# 3xOuts.net
KiCad netlist of a schematic drawn in Altium Designer
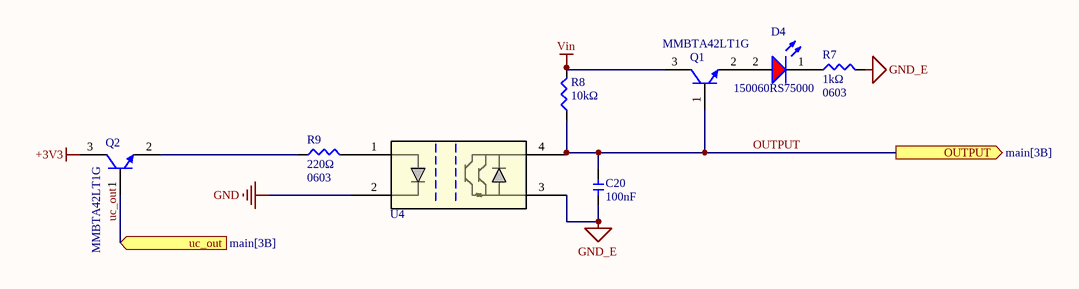
[diagram p0: 3xOuts.SchDoc]

(export (version "E")
  (design (tool "Eeschema 10.0.6"))
  (components
    (comp (ref "C20")
      (value "100nF")
      (footprint "0603_cap")
      (fields (field (name "Comment") "0603_100nF"))
      (libsource (lib "generic") (part "0603_100nF"))
    )
    (comp (ref "D4")
      (value "150060RS75000")
      (footprint "WL-SMCW_0603_150060xx75000")
      (libsource (lib "Altium Content Vault") (part "LED_Red_2A-1K"))
    )
    (comp (ref "Q1")
      (value "MMBTA42LT1G")
      (footprint "ONSC-SOT-23-3-318-08_V")
      (description "High Voltage Transistor, NPN Silicon, 3-Pin SOT-23, Pb-Free, Tape and Reel")
      (fields (field (name "MANUFACTURER") "On Semiconductor"))
      (libsource (lib "Altium Content Vault") (part "ONSC-NPN-B1E2C3-3"))
    )
    (comp (ref "Q2")
      (value "MMBTA42LT1G")
      (footprint "ONSC-SOT-23-3-318-08_V")
      (description "High Voltage Transistor, NPN Silicon, 3-Pin SOT-23, Pb-Free, Tape and Reel")
      (fields (field (name "MANUFACTURER") "On Semiconductor"))
      (libsource (lib "Altium Content Vault") (part "ONSC-NPN-B1E2C3-3"))
    )
    (comp (ref "R7")
      (value "1kΩ")
      (footprint "0603-smd")
      (fields (field (name "POWER") "W") (field (name "PACKAGE") "0603") (field (name "Comment") "0603_1K"))
      (libsource (lib "generic") (part "0603_1K"))
    )
    (comp (ref "R8")
      (value "10kΩ")
      (footprint "0603-smd")
      (fields (field (name "POWER") "W") (field (name "Comment") "0603_10K"))
      (libsource (lib "generic") (part "0603_10K"))
    )
    (comp (ref "R9")
      (value "220Ω")
      (footprint "0603-smd")
      (fields (field (name "POWER") "W") (field (name "PACKAGE") "0603") (field (name "Comment") "0603_220R"))
      (libsource (lib "generic") (part "0603_220R"))
    )
    (comp (ref "U4")
      (value "LTV-352T")
      (footprint "IC4_LTV-352T_LTO-M")
      (description "LTV Series Single Channel 300V 3750 Vrms Transistor Output Optocoupler SMT DIP-4")
      (fields (field (name "MANUFACTURER") "Vishay Lite-On"))
      (libsource (lib "generic") (part "LTV-352T"))
    )
  )
  (nets
    (net (code "1") (name "+3V3") (class "Default")
      (node (ref "Q2") (pin "3") (pinfunction "C_3") (pintype "passive"))
    )
    (net (code "2") (name "/OUTPUT") (class "Default")
      (node (ref "C20") (pin "2") (pinfunction "2_2") (pintype "passive"))
      (node (ref "Q1") (pin "1") (pinfunction "B_1") (pintype "passive"))
      (node (ref "R8") (pin "1") (pinfunction "1_1") (pintype "passive"))
      (node (ref "U4") (pin "4") (pinfunction "4_4") (pintype "passive"))
    )
    (net (code "3") (name "/uc_out") (class "Default")
      (node (ref "Q2") (pin "1") (pinfunction "B_1") (pintype "passive"))
    )
    (net (code "4") (name "GND") (class "Default")
      (node (ref "U4") (pin "2") (pinfunction "2_2") (pintype "passive"))
    )
    (net (code "5") (name "GND_E") (class "Default")
      (node (ref "C20") (pin "1") (pinfunction "1_1") (pintype "passive"))
      (node (ref "R7") (pin "2") (pinfunction "2_2") (pintype "passive"))
      (node (ref "U4") (pin "3") (pinfunction "3_3") (pintype "passive"))
    )
    (net (code "6") (name "Net-(D4-A)") (class "Default")
      (node (ref "D4") (pin "2") (pinfunction "A_2") (pintype "passive"))
      (node (ref "Q1") (pin "2") (pinfunction "E_2") (pintype "passive"))
    )
    (net (code "7") (name "Net-(D4-K)") (class "Default")
      (node (ref "D4") (pin "1") (pinfunction "K_1") (pintype "passive"))
      (node (ref "R7") (pin "1") (pinfunction "1_1") (pintype "passive"))
    )
    (net (code "8") (name "Net-(Q2-E)") (class "Default")
      (node (ref "Q2") (pin "2") (pinfunction "E_2") (pintype "passive"))
      (node (ref "R9") (pin "1") (pinfunction "1_1") (pintype "passive"))
    )
    (net (code "9") (name "Net-(R9-Pad2)") (class "Default")
      (node (ref "R9") (pin "2") (pinfunction "2_2") (pintype "passive"))
      (node (ref "U4") (pin "1") (pinfunction "1_1") (pintype "passive"))
    )
    (net (code "10") (name "Vin") (class "Default")
      (node (ref "Q1") (pin "3") (pinfunction "C_3") (pintype "passive"))
      (node (ref "R8") (pin "2") (pinfunction "2_2") (pintype "passive"))
    )
  )
)
